# OSP_Carrier_V8_PMIC_Audio.net
KiCad netlist of a schematic drawn in Altium Designer
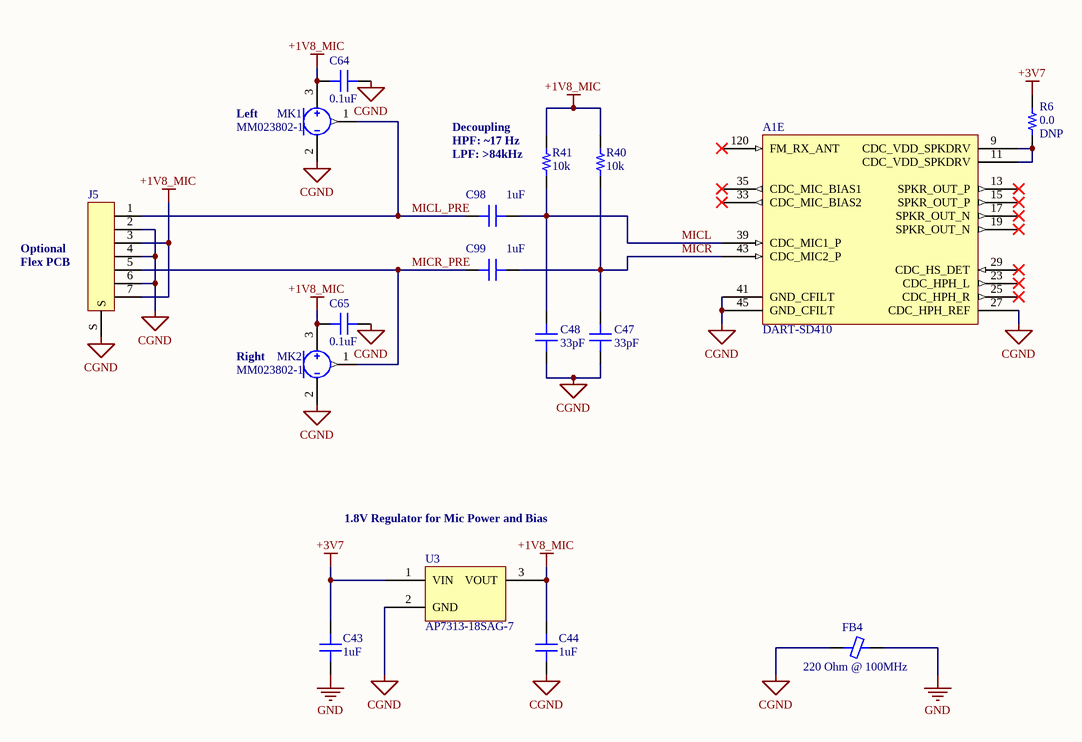
[diagram p0: OSP_Carrier_V8_PMIC_Audio.SchDoc]

(export (version "E")
  (design (tool "Eeschema 10.0.6"))
  (components
    (comp (ref "A1")
      (value "DART-SD410")
      (footprint "DART-SD410")
      (description "Variscite DART-SD410 System on Module")
      (libsource (lib "DART-SD410") (part "DART-SD410"))
    )
    (comp (ref "C43")
      (value "1uF")
      (footprint "CAP 0402/1005")
      (description "CAP CER 1UF 10V X5R 0402")
      (fields
        (field (name "PART NUMBER") "GRM155R61A105KE15D")
        (field (name "MANUFACTURER") "Murata Electronics North America")
      )
      (libsource (lib "Celestial Library Database") (part "Capacitor"))
    )
    (comp (ref "C44")
      (value "1uF")
      (footprint "CAP 0402/1005")
      (description "CAP CER 1UF 10V X5R 0402")
      (fields
        (field (name "PART NUMBER") "GRM155R61A105KE15D")
        (field (name "MANUFACTURER") "Murata Electronics North America")
      )
      (libsource (lib "Celestial Library Database") (part "Capacitor"))
    )
    (comp (ref "C47")
      (value "33pF")
      (footprint "CAP 0402/1005")
      (description "CAP CER 33PF 50V C0G 0402")
      (fields
        (field (name "PART NUMBER") "C1005C0G1H330J050BA")
        (field (name "MANUFACTURER") "TDK Corporation")
      )
      (libsource (lib "Celestial Library Database") (part "Capacitor"))
    )
    (comp (ref "C48")
      (value "33pF")
      (footprint "CAP 0402/1005")
      (description "CAP CER 33PF 50V C0G 0402")
      (fields
        (field (name "PART NUMBER") "C1005C0G1H330J050BA")
        (field (name "MANUFACTURER") "TDK Corporation")
      )
      (libsource (lib "Celestial Library Database") (part "Capacitor"))
    )
    (comp (ref "C64")
      (value "0.1uF")
      (footprint "CAP 0402/1005")
      (description "CAP CER 0.1UF 50V X7R 0402")
      (fields
        (field (name "PART NUMBER") "C1005X7R1H104K050BB")
        (field (name "MANUFACTURER") "TDK Corporation")
      )
      (libsource (lib "Celestial Library Database") (part "Capacitor"))
    )
    (comp (ref "C65")
      (value "0.1uF")
      (footprint "CAP 0402/1005")
      (description "CAP CER 0.1UF 50V X7R 0402")
      (fields
        (field (name "PART NUMBER") "C1005X7R1H104K050BB")
        (field (name "MANUFACTURER") "TDK Corporation")
      )
      (libsource (lib "Celestial Library Database") (part "Capacitor"))
    )
    (comp (ref "C98")
      (value "1uF")
      (footprint "CAP 0603/1608")
      (description "CAP CER 1UF 25V X7R 0603")
      (fields
        (field (name "PART NUMBER") "C1608X7R1E105K080AB")
        (field (name "MANUFACTURER") "TDK Corporation")
      )
      (libsource (lib "Celestial Library Database") (part "Capacitor"))
    )
    (comp (ref "C99")
      (value "1uF")
      (footprint "CAP 0603/1608")
      (description "CAP CER 1UF 25V X7R 0603")
      (fields
        (field (name "PART NUMBER") "C1608X7R1E105K080AB")
        (field (name "MANUFACTURER") "TDK Corporation")
      )
      (libsource (lib "Celestial Library Database") (part "Capacitor"))
    )
    (comp (ref "FB4")
      (value "220 Ohm @ 100MHz")
      (footprint "FER 0402/1005")
      (description "FERRITE CHIP 220 OHM 500MA 0402")
      (fields
        (field (name "PART NUMBER") "CIM05U221NC")
        (field (name "MANUFACTURER") "Samsung Electro-Mechanics America, Inc.")
      )
      (libsource (lib "Celestial Library Database") (part "Ferrite Chip"))
    )
    (comp (ref "J5")
      (value "FFC")
      (footprint "HIROSE_FH58M-7S-0.25SHW-99")
      (description "Hirose FH58M-7S-0.25SHW(99) 7-pin Top+Bottom Contact FFC Connector")
      (libsource (lib "OSP_Symbols") (part "HIROSE_FH58M-7S-0.25SHW-99"))
    )
    (comp (ref "MK1")
      (value "MM023802-1")
      (footprint "MEMS_MIC")
      (description "DB Unlimited MM023802-1 Knowles-Style Bottom Port MEMS Microphone")
      (libsource (lib "OSP_Symbols_Master") (part "DBU_MIC_MEMS_MM023802-1"))
    )
    (comp (ref "MK2")
      (value "MM023802-1")
      (footprint "MEMS_MIC")
      (description "DB Unlimited MM023802-1 Knowles-Style Bottom Port MEMS Microphone")
      (libsource (lib "OSP_Symbols_Master") (part "DBU_MIC_MEMS_MM023802-1"))
    )
    (comp (ref "R6")
      (value "0.0")
      (footprint "RES 0603/1608")
      (description "RES SMD 0.0 OHM JUMPER 1/4W 0603")
      (fields
        (field (name "PART NUMBER") "CRCW06030000Z0EAHP")
        (field (name "MANUFACTURER") "Vishay Dale")
        (field (name "DNP") "DNP")
      )
      (libsource (lib "Celestial Library Database") (part "Resistor"))
    )
    (comp (ref "R40")
      (value "10k")
      (footprint "RES 0402/1005")
      (description "RES SMD 10K OHM 1% 1/10W 0402")
      (fields
        (field (name "PART NUMBER") "ERJ-2RKF1002X")
        (field (name "MANUFACTURER") "Panasonic Electronic Components")
      )
      (libsource (lib "Celestial Library Database") (part "Resistor"))
    )
    (comp (ref "R41")
      (value "10k")
      (footprint "RES 0402/1005")
      (description "RES SMD 10K OHM 1% 1/10W 0402")
      (fields
        (field (name "PART NUMBER") "ERJ-2RKF1002X")
        (field (name "MANUFACTURER") "Panasonic Electronic Components")
      )
      (libsource (lib "Celestial Library Database") (part "Resistor"))
    )
    (comp (ref "U3")
      (value "AP7313-18SAG-7")
      (footprint "DIODES SOT-23-3")
      (description "IC REG LDO 1.8V 0.15A SOT23-3")
      (fields (field (name "MANUFACTURER") "Diodes Incorporated"))
      (libsource (lib "Celestial Library Database") (part "Diodes Inc AP7313"))
    )
  )
  (nets
    (net (code "1") (name "+1V8_MIC") (class "Default")
      (node (ref "C44") (pin "1") (pinfunction "1_1") (pintype "passive"))
      (node (ref "C64") (pin "2") (pinfunction "2_2") (pintype "passive"))
      (node (ref "C65") (pin "2") (pinfunction "2_2") (pintype "passive"))
      (node (ref "J5") (pin "3") (pintype "passive"))
      (node (ref "J5") (pin "7") (pintype "passive"))
      (node (ref "MK1") (pin "3") (pinfunction "VDD_3") (pintype "power_in"))
      (node (ref "MK2") (pin "3") (pinfunction "VDD_3") (pintype "power_in"))
      (node (ref "R40") (pin "2") (pinfunction "2_2") (pintype "passive"))
      (node (ref "R41") (pin "2") (pinfunction "2_2") (pintype "passive"))
      (node (ref "U3") (pin "3") (pinfunction "VOUT_3") (pintype "passive"))
    )
    (net (code "2") (name "+3V7") (class "Default")
      (node (ref "C43") (pin "1") (pinfunction "1_1") (pintype "passive"))
      (node (ref "R6") (pin "2") (pinfunction "2_2") (pintype "passive"))
      (node (ref "U3") (pin "1") (pinfunction "VIN_1") (pintype "passive"))
    )
    (net (code "3") (name "/MICL") (class "Default")
      (node (ref "A1") (pin "39") (pinfunction "CDC_MIC1_P_39") (pintype "input"))
      (node (ref "C48") (pin "2") (pinfunction "2_2") (pintype "passive"))
      (node (ref "C98") (pin "1") (pinfunction "1_1") (pintype "passive"))
      (node (ref "R41") (pin "1") (pinfunction "1_1") (pintype "passive"))
    )
    (net (code "4") (name "/MICL_PRE") (class "Default")
      (node (ref "C98") (pin "2") (pinfunction "2_2") (pintype "passive"))
      (node (ref "J5") (pin "1") (pintype "passive"))
      (node (ref "MK1") (pin "1") (pintype "output"))
    )
    (net (code "5") (name "/MICR") (class "Default")
      (node (ref "A1") (pin "43") (pinfunction "CDC_MIC2_P_43") (pintype "input"))
      (node (ref "C47") (pin "2") (pinfunction "2_2") (pintype "passive"))
      (node (ref "C99") (pin "1") (pinfunction "1_1") (pintype "passive"))
      (node (ref "R40") (pin "1") (pinfunction "1_1") (pintype "passive"))
    )
    (net (code "6") (name "/MICR_PRE") (class "Default")
      (node (ref "C99") (pin "2") (pinfunction "2_2") (pintype "passive"))
      (node (ref "J5") (pin "5") (pintype "passive"))
      (node (ref "MK2") (pin "1") (pintype "output"))
    )
    (net (code "7") (name "CGND") (class "Default")
      (node (ref "A1") (pin "27") (pinfunction "CDC_HPH_REF_27") (pintype "power_in"))
      (node (ref "A1") (pin "41") (pinfunction "GND_CFILT_41") (pintype "power_in"))
      (node (ref "A1") (pin "45") (pinfunction "GND_CFILT_45") (pintype "power_in"))
      (node (ref "C44") (pin "2") (pinfunction "2_2") (pintype "passive"))
      (node (ref "C47") (pin "1") (pinfunction "1_1") (pintype "passive"))
      (node (ref "C48") (pin "1") (pinfunction "1_1") (pintype "passive"))
      (node (ref "C64") (pin "1") (pinfunction "1_1") (pintype "passive"))
      (node (ref "C65") (pin "1") (pinfunction "1_1") (pintype "passive"))
      (node (ref "FB4") (pin "1") (pinfunction "1_1") (pintype "passive"))
      (node (ref "J5") (pin "2") (pintype "passive"))
      (node (ref "J5") (pin "4") (pintype "passive"))
      (node (ref "J5") (pin "6") (pintype "passive"))
      (node (ref "J5") (pin "S") (pinfunction "S_S") (pintype "power_in"))
      (node (ref "MK1") (pin "2") (pinfunction "GND_2") (pintype "power_in"))
      (node (ref "MK2") (pin "2") (pinfunction "GND_2") (pintype "power_in"))
      (node (ref "U3") (pin "2") (pinfunction "GND_2") (pintype "passive"))
    )
    (net (code "8") (name "GND") (class "Default")
      (node (ref "C43") (pin "2") (pinfunction "2_2") (pintype "passive"))
      (node (ref "FB4") (pin "2") (pinfunction "2_2") (pintype "passive"))
    )
    (net (code "9") (name "Net-(A1E-CDC_VDD_SPKDRV-Pad11)") (class "Default")
      (node (ref "A1") (pin "11") (pinfunction "CDC_VDD_SPKDRV_11") (pintype "power_in"))
      (node (ref "A1") (pin "9") (pinfunction "CDC_VDD_SPKDRV_9") (pintype "power_in"))
      (node (ref "R6") (pin "1") (pinfunction "1_1") (pintype "passive"))
    )
    (net (code "10") (name "unconnected-(A1E-CDC_HPH_L-Pad23)") (class "Default")
      (node (ref "A1") (pin "23") (pinfunction "CDC_HPH_L_23") (pintype "output+no_connect"))
    )
    (net (code "11") (name "unconnected-(A1E-CDC_HPH_R-Pad25)") (class "Default")
      (node (ref "A1") (pin "25") (pinfunction "CDC_HPH_R_25") (pintype "output+no_connect"))
    )
    (net (code "12") (name "unconnected-(A1E-CDC_HS_DET-Pad29)") (class "Default")
      (node (ref "A1") (pin "29") (pinfunction "CDC_HS_DET_29") (pintype "input+no_connect"))
    )
    (net (code "13") (name "unconnected-(A1E-CDC_MIC_BIAS1-Pad35)") (class "Default")
      (node (ref "A1") (pin "35") (pinfunction "CDC_MIC_BIAS1_35") (pintype "output+no_connect"))
    )
    (net (code "14") (name "unconnected-(A1E-CDC_MIC_BIAS2-Pad33)") (class "Default")
      (node (ref "A1") (pin "33") (pinfunction "CDC_MIC_BIAS2_33") (pintype "output+no_connect"))
    )
    (net (code "15") (name "unconnected-(A1E-FM_RX_ANT-Pad120)") (class "Default")
      (node (ref "A1") (pin "120") (pinfunction "FM_RX_ANT_120") (pintype "input+no_connect"))
    )
    (net (code "16") (name "unconnected-(A1E-SPKR_OUT_N-Pad17)") (class "Default")
      (node (ref "A1") (pin "17") (pinfunction "SPKR_OUT_N_17") (pintype "output+no_connect"))
    )
    (net (code "17") (name "unconnected-(A1E-SPKR_OUT_N-Pad19)") (class "Default")
      (node (ref "A1") (pin "19") (pinfunction "SPKR_OUT_N_19") (pintype "output+no_connect"))
    )
    (net (code "18") (name "unconnected-(A1E-SPKR_OUT_P-Pad13)") (class "Default")
      (node (ref "A1") (pin "13") (pinfunction "SPKR_OUT_P_13") (pintype "output+no_connect"))
    )
    (net (code "19") (name "unconnected-(A1E-SPKR_OUT_P-Pad15)") (class "Default")
      (node (ref "A1") (pin "15") (pinfunction "SPKR_OUT_P_15") (pintype "output+no_connect"))
    )
  )
)
